# 8-ultrasonic-to-nano.net
KiCad netlist of a schematic drawn in EAGLE
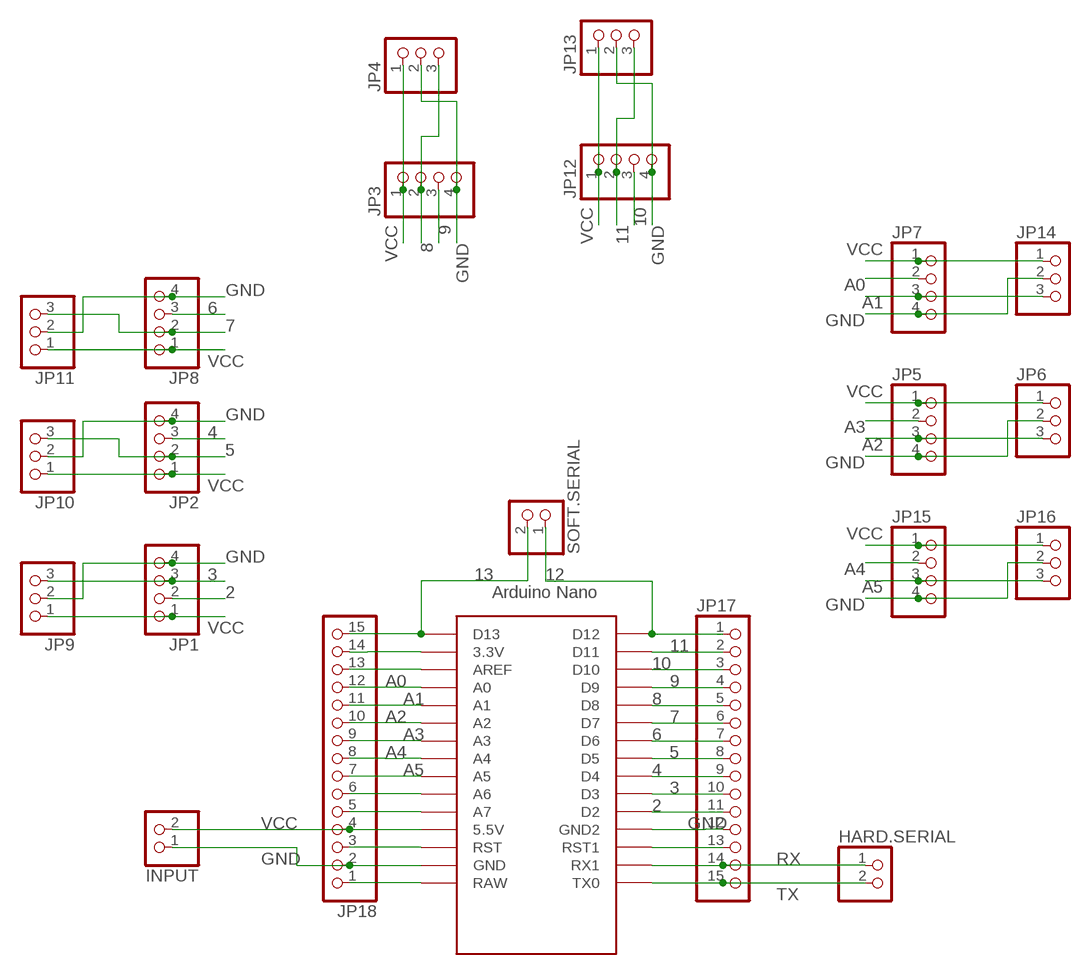
[diagram p0: schematic, sheet 1]

(export (version "E")
  (design (tool "Eeschema 10.0.6"))
  (components
    (comp (ref "HARD.SERIAL")
      (value "PINHD-2_DATA")
      (footprint "eagle-import:1X02_DATA")
      (libsource (lib "eagle-import") (part "PINHD-2_DATA"))
    )
    (comp (ref "INPUT")
      (value "PINHD-2_DATA")
      (footprint "eagle-import:1X02_DATA")
      (libsource (lib "eagle-import") (part "PINHD-2_DATA"))
    )
    (comp (ref "JP1")
      (value "PINHD-4_DATA")
      (footprint "eagle-import:1X04_DATA")
      (libsource (lib "eagle-import") (part "PINHD-4_DATA"))
    )
    (comp (ref "JP2")
      (value "PINHD-4_DATA")
      (footprint "eagle-import:1X04_DATA")
      (libsource (lib "eagle-import") (part "PINHD-4_DATA"))
    )
    (comp (ref "JP3")
      (value "PINHD-4_DATA")
      (footprint "eagle-import:1X04_DATA")
      (libsource (lib "eagle-import") (part "PINHD-4_DATA"))
    )
    (comp (ref "JP4")
      (value "PINHD-3_DATA")
      (footprint "eagle-import:1X03_DATA")
      (libsource (lib "eagle-import") (part "PINHD-3_DATA"))
    )
    (comp (ref "JP5")
      (value "PINHD-4_DATA")
      (footprint "eagle-import:1X04_DATA")
      (libsource (lib "eagle-import") (part "PINHD-4_DATA"))
    )
    (comp (ref "JP6")
      (value "PINHD-3_DATA")
      (footprint "eagle-import:1X03_DATA")
      (libsource (lib "eagle-import") (part "PINHD-3_DATA"))
    )
    (comp (ref "JP7")
      (value "PINHD-4_DATA")
      (footprint "eagle-import:1X04_DATA")
      (libsource (lib "eagle-import") (part "PINHD-4_DATA"))
    )
    (comp (ref "JP8")
      (value "PINHD-4_DATA")
      (footprint "eagle-import:1X04_DATA")
      (libsource (lib "eagle-import") (part "PINHD-4_DATA"))
    )
    (comp (ref "JP9")
      (value "PINHD-3_DATA")
      (footprint "eagle-import:1X03_DATA")
      (libsource (lib "eagle-import") (part "PINHD-3_DATA"))
    )
    (comp (ref "JP10")
      (value "PINHD-3_DATA")
      (footprint "eagle-import:1X03_DATA")
      (libsource (lib "eagle-import") (part "PINHD-3_DATA"))
    )
    (comp (ref "JP11")
      (value "PINHD-3_DATA")
      (footprint "eagle-import:1X03_DATA")
      (libsource (lib "eagle-import") (part "PINHD-3_DATA"))
    )
    (comp (ref "JP12")
      (value "PINHD-4_DATA")
      (footprint "eagle-import:1X04_DATA")
      (libsource (lib "eagle-import") (part "PINHD-4_DATA"))
    )
    (comp (ref "JP13")
      (value "PINHD-3_DATA")
      (footprint "eagle-import:1X03_DATA")
      (libsource (lib "eagle-import") (part "PINHD-3_DATA"))
    )
    (comp (ref "JP14")
      (value "PINHD-3_DATA")
      (footprint "eagle-import:1X03_DATA")
      (libsource (lib "eagle-import") (part "PINHD-3_DATA"))
    )
    (comp (ref "JP15")
      (value "PINHD-4_DATA")
      (footprint "eagle-import:1X04_DATA")
      (libsource (lib "eagle-import") (part "PINHD-4_DATA"))
    )
    (comp (ref "JP16")
      (value "PINHD-3_DATA")
      (footprint "eagle-import:1X03_DATA")
      (libsource (lib "eagle-import") (part "PINHD-3_DATA"))
    )
    (comp (ref "JP17")
      (value "PINHD-1X15")
      (footprint "eagle-import:1X15")
      (libsource (lib "eagle-import") (part "PINHD-1X15"))
    )
    (comp (ref "JP18")
      (value "PINHD-1X15")
      (footprint "eagle-import:1X15")
      (libsource (lib "eagle-import") (part "PINHD-1X15"))
    )
    (comp (ref "SOFT.SERIAL")
      (value "PINHD-2_DATA")
      (footprint "eagle-import:1X02_DATA")
      (libsource (lib "eagle-import") (part "PINHD-2_DATA"))
    )
    (comp (ref "U$1")
      (value "ARDUINO_NANO")
      (footprint "eagle-import:NANO")
      (libsource (lib "eagle-import") (part "ARDUINO_NANO"))
    )
  )
  (nets
    (net (code "1") (name "/2") (class "Default")
      (node (ref "JP1") (pin "2") (pinfunction "2_2") (pintype "passive"))
      (node (ref "JP17") (pin "11") (pinfunction "11_11") (pintype "passive"))
      (node (ref "U$1") (pin "D2") (pinfunction "D2_D2") (pintype "bidirectional"))
    )
    (net (code "2") (name "/3") (class "Default")
      (node (ref "JP1") (pin "3") (pinfunction "3_3") (pintype "passive"))
      (node (ref "JP17") (pin "10") (pinfunction "10_10") (pintype "passive"))
      (node (ref "JP9") (pin "3") (pinfunction "3_3") (pintype "passive"))
      (node (ref "U$1") (pin "D3") (pinfunction "D3_D3") (pintype "bidirectional"))
    )
    (net (code "3") (name "/4") (class "Default")
      (node (ref "JP17") (pin "9") (pinfunction "9_9") (pintype "passive"))
      (node (ref "JP2") (pin "3") (pinfunction "3_3") (pintype "passive"))
      (node (ref "U$1") (pin "D4") (pinfunction "D4_D4") (pintype "bidirectional"))
    )
    (net (code "4") (name "/5") (class "Default")
      (node (ref "JP10") (pin "3") (pinfunction "3_3") (pintype "passive"))
      (node (ref "JP17") (pin "8") (pinfunction "8_8") (pintype "passive"))
      (node (ref "JP2") (pin "2") (pinfunction "2_2") (pintype "passive"))
      (node (ref "U$1") (pin "D5") (pinfunction "D5_D5") (pintype "bidirectional"))
    )
    (net (code "5") (name "/6") (class "Default")
      (node (ref "JP17") (pin "7") (pinfunction "7_7") (pintype "passive"))
      (node (ref "JP8") (pin "3") (pinfunction "3_3") (pintype "passive"))
      (node (ref "U$1") (pin "D6") (pinfunction "D6_D6") (pintype "bidirectional"))
    )
    (net (code "6") (name "/7") (class "Default")
      (node (ref "JP11") (pin "3") (pinfunction "3_3") (pintype "passive"))
      (node (ref "JP17") (pin "6") (pinfunction "6_6") (pintype "passive"))
      (node (ref "JP8") (pin "2") (pinfunction "2_2") (pintype "passive"))
      (node (ref "U$1") (pin "D7") (pinfunction "D7_D7") (pintype "bidirectional"))
    )
    (net (code "7") (name "/8") (class "Default")
      (node (ref "JP17") (pin "5") (pinfunction "5_5") (pintype "passive"))
      (node (ref "JP3") (pin "2") (pinfunction "2_2") (pintype "passive"))
      (node (ref "JP4") (pin "3") (pinfunction "3_3") (pintype "passive"))
      (node (ref "U$1") (pin "D8") (pinfunction "D8_D8") (pintype "bidirectional"))
    )
    (net (code "8") (name "/9") (class "Default")
      (node (ref "JP17") (pin "4") (pinfunction "4_4") (pintype "passive"))
      (node (ref "JP3") (pin "3") (pinfunction "3_3") (pintype "passive"))
      (node (ref "U$1") (pin "D9") (pinfunction "D9_D9") (pintype "bidirectional"))
    )
    (net (code "9") (name "/10") (class "Default")
      (node (ref "JP12") (pin "3") (pinfunction "3_3") (pintype "passive"))
      (node (ref "JP17") (pin "3") (pinfunction "3_3") (pintype "passive"))
      (node (ref "U$1") (pin "D10") (pinfunction "D10_D10") (pintype "bidirectional"))
    )
    (net (code "10") (name "/11") (class "Default")
      (node (ref "JP12") (pin "2") (pinfunction "2_2") (pintype "passive"))
      (node (ref "JP13") (pin "3") (pinfunction "3_3") (pintype "passive"))
      (node (ref "JP17") (pin "2") (pinfunction "2_2") (pintype "passive"))
      (node (ref "U$1") (pin "D11") (pinfunction "D11_D11") (pintype "bidirectional"))
    )
    (net (code "11") (name "/12") (class "Default")
      (node (ref "JP17") (pin "1") (pinfunction "1_1") (pintype "passive"))
      (node (ref "SOFT.SERIAL") (pin "1") (pinfunction "1_1") (pintype "passive"))
      (node (ref "U$1") (pin "D12") (pinfunction "D12_D12") (pintype "bidirectional"))
    )
    (net (code "12") (name "/13") (class "Default")
      (node (ref "JP18") (pin "15") (pinfunction "15_15") (pintype "passive"))
      (node (ref "SOFT.SERIAL") (pin "2") (pinfunction "2_2") (pintype "passive"))
      (node (ref "U$1") (pin "D13") (pinfunction "D13_D13") (pintype "bidirectional"))
    )
    (net (code "13") (name "/A0") (class "Default")
      (node (ref "JP18") (pin "12") (pinfunction "12_12") (pintype "passive"))
      (node (ref "JP7") (pin "2") (pinfunction "2_2") (pintype "passive"))
      (node (ref "U$1") (pin "A0") (pinfunction "A0_A0") (pintype "bidirectional"))
    )
    (net (code "14") (name "/A1") (class "Default")
      (node (ref "JP14") (pin "3") (pinfunction "3_3") (pintype "passive"))
      (node (ref "JP18") (pin "11") (pinfunction "11_11") (pintype "passive"))
      (node (ref "JP7") (pin "3") (pinfunction "3_3") (pintype "passive"))
      (node (ref "U$1") (pin "A1") (pinfunction "A1_A1") (pintype "bidirectional"))
    )
    (net (code "15") (name "/A2") (class "Default")
      (node (ref "JP18") (pin "10") (pinfunction "10_10") (pintype "passive"))
      (node (ref "JP5") (pin "3") (pinfunction "3_3") (pintype "passive"))
      (node (ref "JP6") (pin "3") (pinfunction "3_3") (pintype "passive"))
      (node (ref "U$1") (pin "A2") (pinfunction "A2_A2") (pintype "bidirectional"))
    )
    (net (code "16") (name "/A3") (class "Default")
      (node (ref "JP18") (pin "9") (pinfunction "9_9") (pintype "passive"))
      (node (ref "JP5") (pin "2") (pinfunction "2_2") (pintype "passive"))
      (node (ref "U$1") (pin "A3") (pinfunction "A3_A3") (pintype "bidirectional"))
    )
    (net (code "17") (name "/A4") (class "Default")
      (node (ref "JP15") (pin "2") (pinfunction "2_2") (pintype "passive"))
      (node (ref "JP18") (pin "8") (pinfunction "8_8") (pintype "passive"))
      (node (ref "U$1") (pin "A4") (pinfunction "A4_A4") (pintype "bidirectional"))
    )
    (net (code "18") (name "/A5") (class "Default")
      (node (ref "JP15") (pin "3") (pinfunction "3_3") (pintype "passive"))
      (node (ref "JP16") (pin "3") (pinfunction "3_3") (pintype "passive"))
      (node (ref "JP18") (pin "7") (pinfunction "7_7") (pintype "passive"))
      (node (ref "U$1") (pin "A5") (pinfunction "A5_A5") (pintype "bidirectional"))
    )
    (net (code "19") (name "/GND") (class "Default")
      (node (ref "INPUT") (pin "1") (pinfunction "1_1") (pintype "passive"))
      (node (ref "JP1") (pin "4") (pinfunction "4_4") (pintype "passive"))
      (node (ref "JP10") (pin "2") (pinfunction "2_2") (pintype "passive"))
      (node (ref "JP11") (pin "2") (pinfunction "2_2") (pintype "passive"))
      (node (ref "JP12") (pin "4") (pinfunction "4_4") (pintype "passive"))
      (node (ref "JP13") (pin "2") (pinfunction "2_2") (pintype "passive"))
      (node (ref "JP14") (pin "2") (pinfunction "2_2") (pintype "passive"))
      (node (ref "JP15") (pin "4") (pinfunction "4_4") (pintype "passive"))
      (node (ref "JP16") (pin "2") (pinfunction "2_2") (pintype "passive"))
      (node (ref "JP17") (pin "12") (pinfunction "12_12") (pintype "passive"))
      (node (ref "JP18") (pin "2") (pinfunction "2_2") (pintype "passive"))
      (node (ref "JP2") (pin "4") (pinfunction "4_4") (pintype "passive"))
      (node (ref "JP3") (pin "4") (pinfunction "4_4") (pintype "passive"))
      (node (ref "JP4") (pin "2") (pinfunction "2_2") (pintype "passive"))
      (node (ref "JP5") (pin "4") (pinfunction "4_4") (pintype "passive"))
      (node (ref "JP6") (pin "2") (pinfunction "2_2") (pintype "passive"))
      (node (ref "JP7") (pin "4") (pinfunction "4_4") (pintype "passive"))
      (node (ref "JP8") (pin "4") (pinfunction "4_4") (pintype "passive"))
      (node (ref "JP9") (pin "2") (pinfunction "2_2") (pintype "passive"))
      (node (ref "U$1") (pin "GND") (pinfunction "GND_GND") (pintype "bidirectional"))
      (node (ref "U$1") (pin "GND1") (pinfunction "GND2_GND1") (pintype "bidirectional"))
    )
    (net (code "20") (name "/RX") (class "Default")
      (node (ref "HARD.SERIAL") (pin "1") (pinfunction "1_1") (pintype "passive"))
      (node (ref "JP17") (pin "14") (pinfunction "14_14") (pintype "passive"))
      (node (ref "U$1") (pin "RX1") (pinfunction "RX1_RX1") (pintype "bidirectional"))
    )
    (net (code "21") (name "/TX") (class "Default")
      (node (ref "HARD.SERIAL") (pin "2") (pinfunction "2_2") (pintype "passive"))
      (node (ref "JP17") (pin "15") (pinfunction "15_15") (pintype "passive"))
      (node (ref "U$1") (pin "TX0") (pinfunction "TX0_TX0") (pintype "bidirectional"))
    )
    (net (code "22") (name "/VCC") (class "Default")
      (node (ref "INPUT") (pin "2") (pinfunction "2_2") (pintype "passive"))
      (node (ref "JP1") (pin "1") (pinfunction "1_1") (pintype "passive"))
      (node (ref "JP10") (pin "1") (pinfunction "1_1") (pintype "passive"))
      (node (ref "JP11") (pin "1") (pinfunction "1_1") (pintype "passive"))
      (node (ref "JP12") (pin "1") (pinfunction "1_1") (pintype "passive"))
      (node (ref "JP13") (pin "1") (pinfunction "1_1") (pintype "passive"))
      (node (ref "JP14") (pin "1") (pinfunction "1_1") (pintype "passive"))
      (node (ref "JP15") (pin "1") (pinfunction "1_1") (pintype "passive"))
      (node (ref "JP16") (pin "1") (pinfunction "1_1") (pintype "passive"))
      (node (ref "JP18") (pin "4") (pinfunction "4_4") (pintype "passive"))
      (node (ref "JP2") (pin "1") (pinfunction "1_1") (pintype "passive"))
      (node (ref "JP3") (pin "1") (pinfunction "1_1") (pintype "passive"))
      (node (ref "JP4") (pin "1") (pinfunction "1_1") (pintype "passive"))
      (node (ref "JP5") (pin "1") (pinfunction "1_1") (pintype "passive"))
      (node (ref "JP6") (pin "1") (pinfunction "1_1") (pintype "passive"))
      (node (ref "JP7") (pin "1") (pinfunction "1_1") (pintype "passive"))
      (node (ref "JP8") (pin "1") (pinfunction "1_1") (pintype "passive"))
      (node (ref "JP9") (pin "1") (pinfunction "1_1") (pintype "passive"))
      (node (ref "U$1") (pin "5V") (pinfunction "5.5V_5V") (pintype "bidirectional"))
    )
    (net (code "23") (name "Net-(JP17-Pad13)") (class "Default")
      (node (ref "JP17") (pin "13") (pinfunction "13_13") (pintype "passive"))
      (node (ref "U$1") (pin "RST1") (pinfunction "RST1_RST1") (pintype "bidirectional"))
    )
    (net (code "24") (name "Net-(JP18-Pad1)") (class "Default")
      (node (ref "JP18") (pin "1") (pinfunction "1_1") (pintype "passive"))
      (node (ref "U$1") (pin "RAW") (pinfunction "RAW_RAW") (pintype "bidirectional"))
    )
    (net (code "25") (name "Net-(JP18-Pad3)") (class "Default")
      (node (ref "JP18") (pin "3") (pinfunction "3_3") (pintype "passive"))
      (node (ref "U$1") (pin "RST") (pinfunction "RST_RST") (pintype "bidirectional"))
    )
    (net (code "26") (name "Net-(JP18-Pad5)") (class "Default")
      (node (ref "JP18") (pin "5") (pinfunction "5_5") (pintype "passive"))
      (node (ref "U$1") (pin "A7") (pinfunction "A7_A7") (pintype "bidirectional"))
    )
    (net (code "27") (name "Net-(JP18-Pad6)") (class "Default")
      (node (ref "JP18") (pin "6") (pinfunction "6_6") (pintype "passive"))
      (node (ref "U$1") (pin "A6") (pinfunction "A6_A6") (pintype "bidirectional"))
    )
    (net (code "28") (name "Net-(JP18-Pad13)") (class "Default")
      (node (ref "JP18") (pin "13") (pinfunction "13_13") (pintype "passive"))
      (node (ref "U$1") (pin "AREF") (pinfunction "AREF_AREF") (pintype "bidirectional"))
    )
    (net (code "29") (name "Net-(JP18-Pad14)") (class "Default")
      (node (ref "JP18") (pin "14") (pinfunction "14_14") (pintype "passive"))
      (node (ref "U$1") (pin "3.3V") (pinfunction "3.3V_3.3V") (pintype "bidirectional"))
    )
  )
)
